# design.net
KiCad netlist of a schematic drawn in Altium Designer
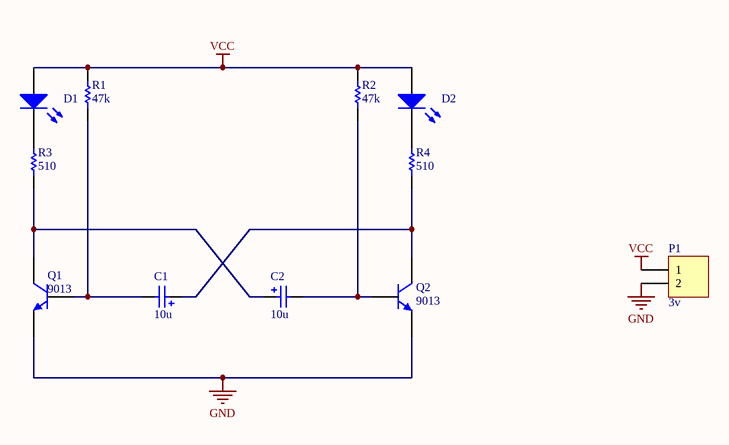
[diagram p0: 谐波振荡器.SchDoc]

(export (version "E")
  (design (tool "Eeschema 10.0.6"))
  (components
    (comp (ref "C1")
      (value "10u")
      (footprint "CAPPR2-5x6.8")
      (description "Polarized Capacitor (Axial)")
      (fields (field (name "PUBLISHER") "Altium Limited"))
      (libsource (lib "Miscellaneous Devices") (part "Cap Pol2"))
    )
    (comp (ref "C2")
      (value "10u")
      (footprint "CAPPR2-5x6.8")
      (description "Polarized Capacitor (Axial)")
      (fields (field (name "PUBLISHER") "Altium Limited"))
      (libsource (lib "Miscellaneous Devices") (part "Cap Pol2"))
    )
    (comp (ref "D1")
      (value "LED0")
      (footprint "CAPPR2-5x6.8")
      (description "Typical INFRARED GaAs LED")
      (fields (field (name "PUBLISHER") "Altium Limited"))
      (libsource (lib "Miscellaneous Devices") (part "LED0"))
    )
    (comp (ref "D2")
      (value "LED0")
      (footprint "CAPPR2-5x6.8")
      (description "Typical INFRARED GaAs LED")
      (fields (field (name "PUBLISHER") "Altium Limited"))
      (libsource (lib "Miscellaneous Devices") (part "LED0"))
    )
    (comp (ref "P1")
      (value "3v")
      (footprint "HDR1X2")
      (description "Header, 2-Pin")
      (fields (field (name "PUBLISHER") "Altium Limited"))
      (libsource (lib "Miscellaneous Connectors") (part "Header 2"))
    )
    (comp (ref "Q1")
      (value "9013")
      (footprint "BCY-W3/E4")
      (description "NPN General Purpose Amplifier")
      (fields (field (name "PUBLISHER") "Altium Limited"))
      (libsource (lib "Miscellaneous Devices") (part "2N3904"))
    )
    (comp (ref "Q2")
      (value "9013")
      (footprint "BCY-W3/E4")
      (description "NPN General Purpose Amplifier")
      (fields (field (name "PUBLISHER") "Altium Limited"))
      (libsource (lib "Miscellaneous Devices") (part "2N3904"))
    )
    (comp (ref "R1")
      (value "47k")
      (footprint "AXIAL-0.3")
      (description "Resistor")
      (fields (field (name "PUBLISHER") "Altium Limited"))
      (libsource (lib "Miscellaneous Devices") (part "Res1"))
    )
    (comp (ref "R2")
      (value "47k")
      (footprint "AXIAL-0.3")
      (description "Resistor")
      (fields (field (name "PUBLISHER") "Altium Limited"))
      (libsource (lib "Miscellaneous Devices") (part "Res1"))
    )
    (comp (ref "R3")
      (value "510")
      (footprint "AXIAL-0.3")
      (description "Resistor")
      (fields (field (name "PUBLISHER") "Altium Limited"))
      (libsource (lib "Miscellaneous Devices") (part "Res1"))
    )
    (comp (ref "R4")
      (value "510")
      (footprint "AXIAL-0.3")
      (description "Resistor")
      (fields (field (name "PUBLISHER") "Altium Limited"))
      (libsource (lib "Miscellaneous Devices") (part "Res1"))
    )
  )
  (nets
    (net (code "1") (name "GND") (class "Default")
      (node (ref "P1") (pin "2") (pinfunction "2_2") (pintype "passive"))
      (node (ref "Q1") (pin "1") (pinfunction "E_1") (pintype "passive"))
      (node (ref "Q2") (pin "1") (pinfunction "E_1") (pintype "passive"))
    )
    (net (code "2") (name "Net-(D1-K)") (class "Default")
      (node (ref "D1") (pin "2") (pinfunction "K_2") (pintype "passive"))
      (node (ref "R3") (pin "2") (pinfunction "2_2") (pintype "passive"))
    )
    (net (code "3") (name "Net-(D2-K)") (class "Default")
      (node (ref "D2") (pin "2") (pinfunction "K_2") (pintype "passive"))
      (node (ref "R4") (pin "2") (pinfunction "2_2") (pintype "passive"))
    )
    (net (code "4") (name "Net-(Q1-B)") (class "Default")
      (node (ref "C1") (pin "2") (pinfunction "2_2") (pintype "passive"))
      (node (ref "Q1") (pin "2") (pinfunction "B_2") (pintype "passive"))
      (node (ref "R1") (pin "1") (pinfunction "1_1") (pintype "passive"))
    )
    (net (code "5") (name "Net-(Q1-C)") (class "Default")
      (node (ref "C2") (pin "1") (pinfunction "1_1") (pintype "passive"))
      (node (ref "Q1") (pin "3") (pinfunction "C_3") (pintype "passive"))
      (node (ref "R3") (pin "1") (pinfunction "1_1") (pintype "passive"))
    )
    (net (code "6") (name "Net-(Q2-B)") (class "Default")
      (node (ref "C2") (pin "2") (pinfunction "2_2") (pintype "passive"))
      (node (ref "Q2") (pin "2") (pinfunction "B_2") (pintype "passive"))
      (node (ref "R2") (pin "1") (pinfunction "1_1") (pintype "passive"))
    )
    (net (code "7") (name "Net-(Q2-C)") (class "Default")
      (node (ref "C1") (pin "1") (pinfunction "1_1") (pintype "passive"))
      (node (ref "Q2") (pin "3") (pinfunction "C_3") (pintype "passive"))
      (node (ref "R4") (pin "1") (pinfunction "1_1") (pintype "passive"))
    )
    (net (code "8") (name "VCC") (class "Default")
      (node (ref "D1") (pin "1") (pinfunction "A_1") (pintype "passive"))
      (node (ref "D2") (pin "1") (pinfunction "A_1") (pintype "passive"))
      (node (ref "P1") (pin "1") (pinfunction "1_1") (pintype "passive"))
      (node (ref "R1") (pin "2") (pinfunction "2_2") (pintype "passive"))
      (node (ref "R2") (pin "2") (pinfunction "2_2") (pintype "passive"))
    )
  )
)
